# 501_GridPos5.net
KiCad netlist of a schematic drawn in Altium Designer
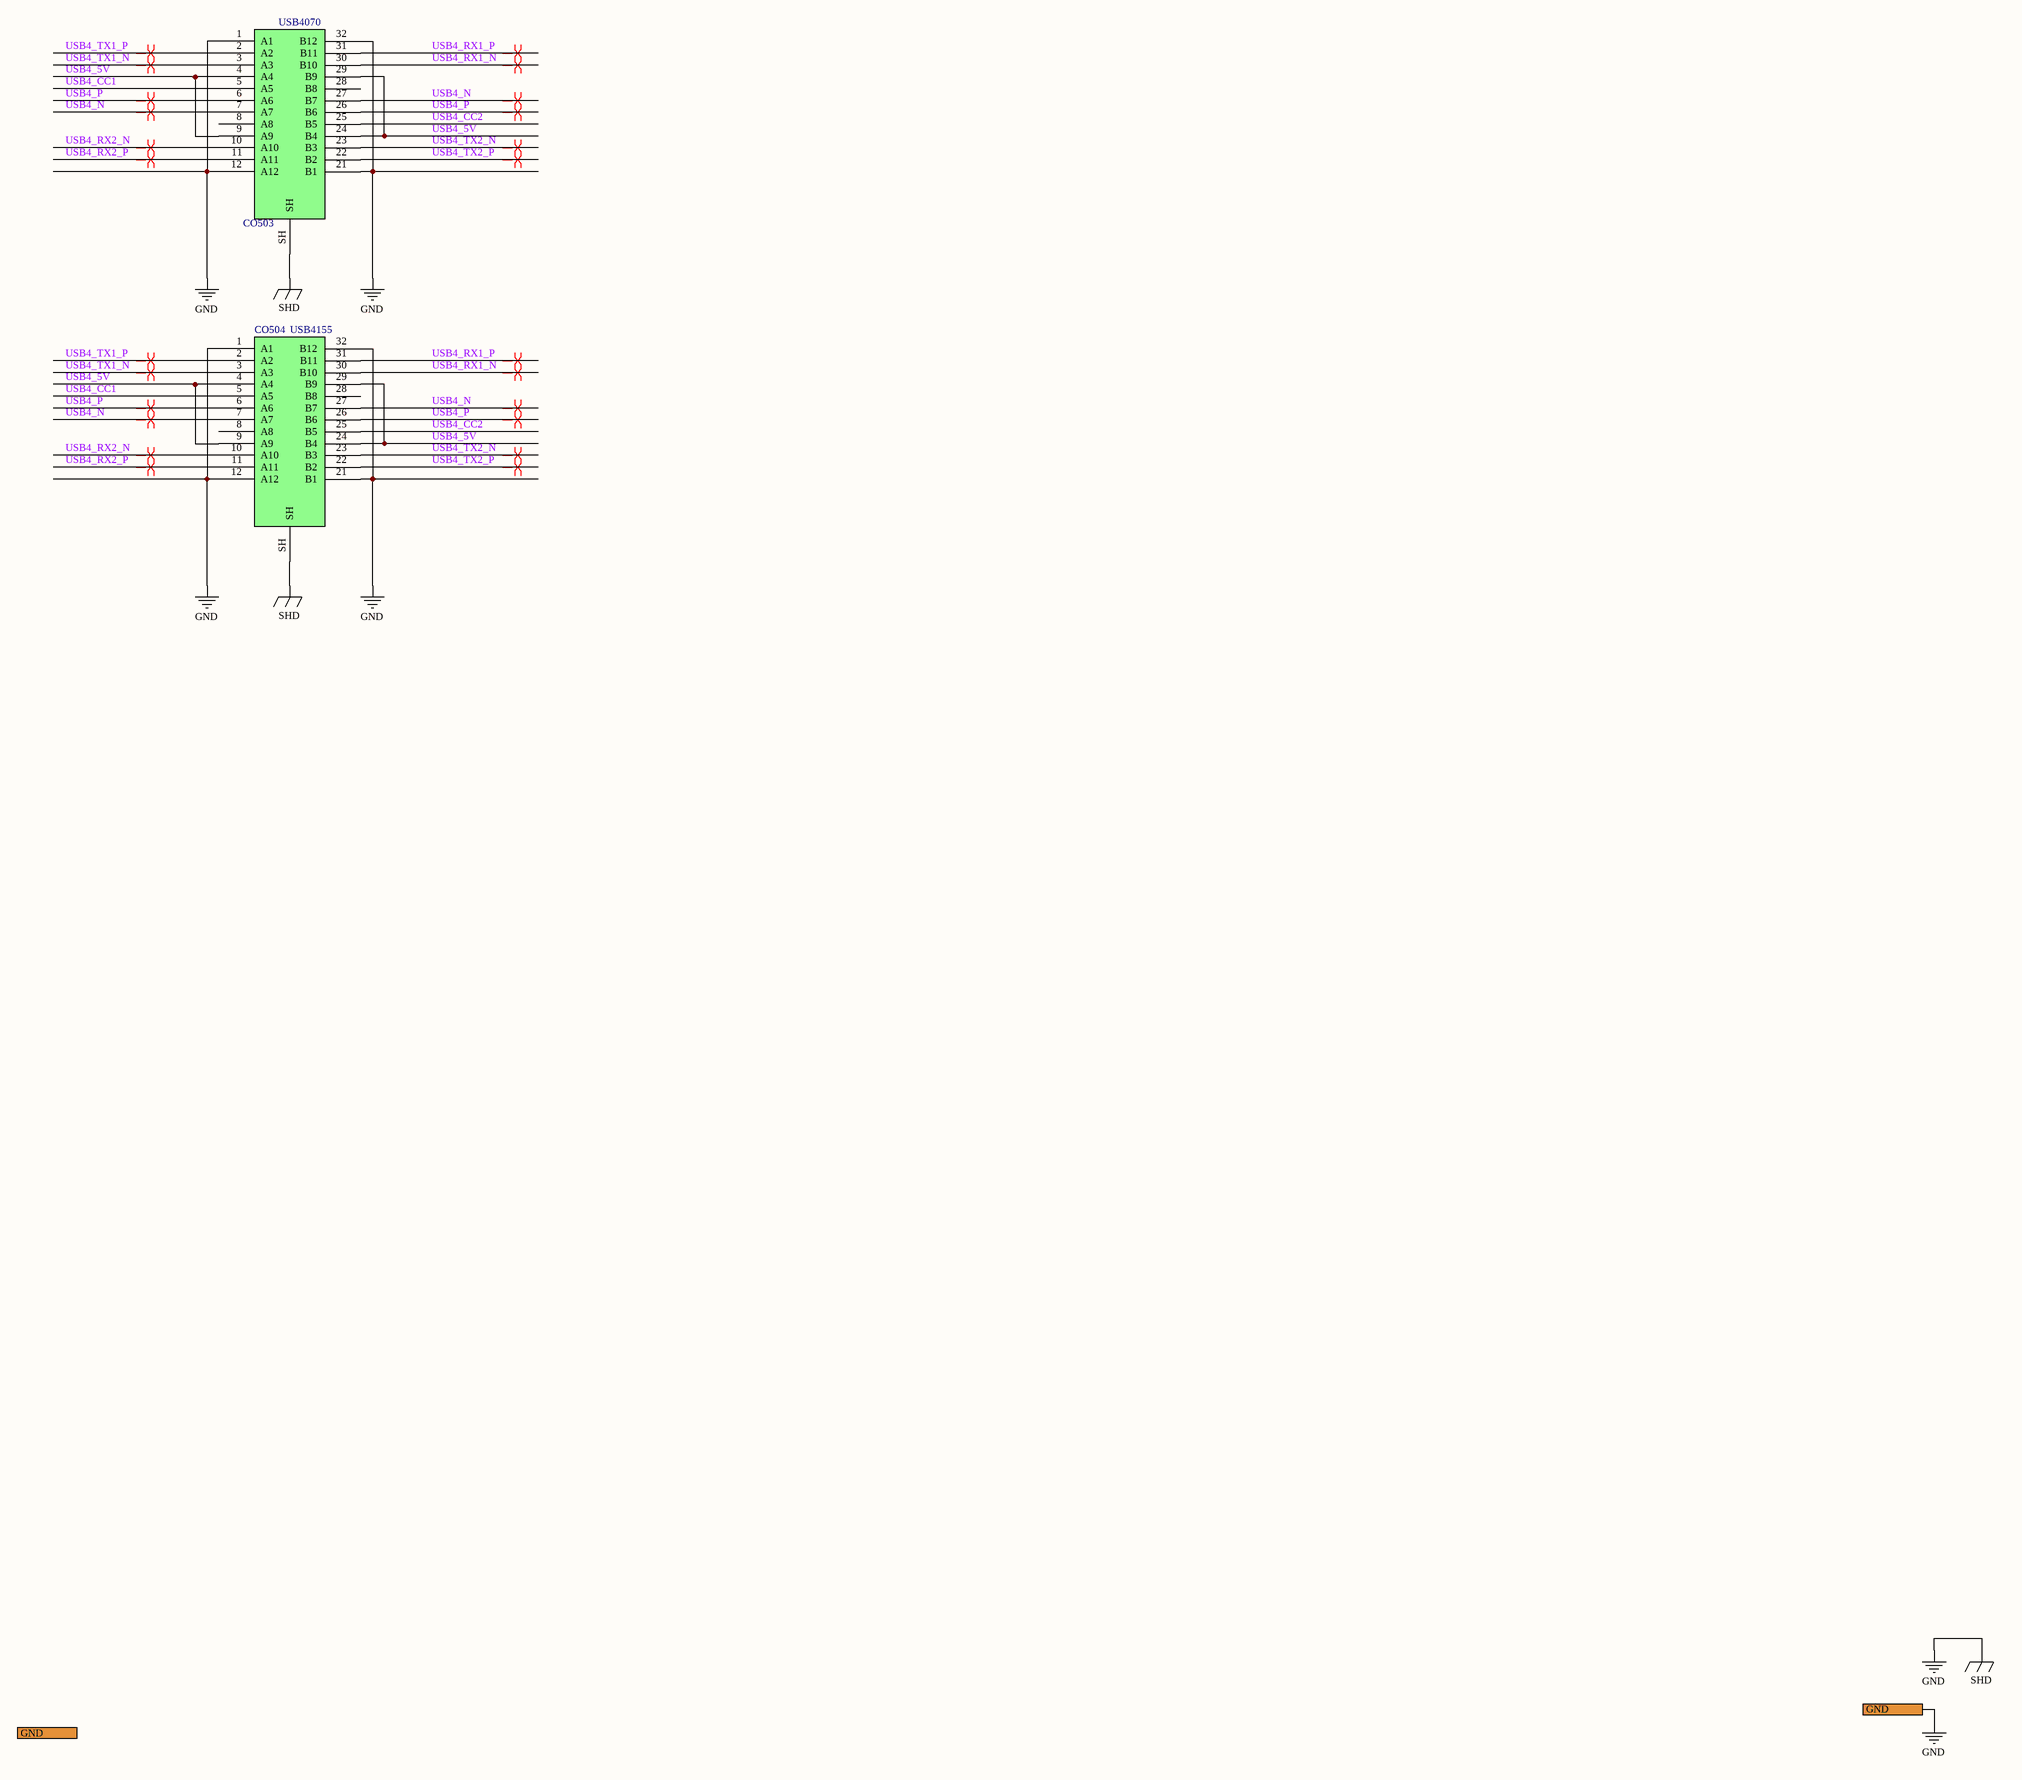
[diagram p0: 501_GridPos5.SchDoc]

(export (version "E")
  (design (tool "Eeschema 10.0.6"))
  (components
    (comp (ref "CO503")
      (value "USB4070")
      (footprint "USB4070-30-C")
      (description "USB C connector Receptacle Vertical")
      (fields
        (field (name "REFVAL") "USB4070")
        (field (name "PART NUMBER") "CO0021")
        (field (name "MANFACTPART") "USB4070-30-C")
      )
      (libsource (lib "GTS_Database") (part "USB-CC"))
    )
    (comp (ref "CO504")
      (value "USB4155")
      (footprint "USB4155-03-C")
      (description "USB C connector Plug Horizontal")
      (fields
        (field (name "REFVAL") "USB4155")
        (field (name "PART NUMBER") "CO0031")
        (field (name "MANFACTPART") "USB4155-03-C")
      )
      (libsource (lib "GTS_Database") (part "USB-CC"))
    )
  )
  (nets
    (net (code "1") (name "/USB4_5V") (class "Default")
      (node (ref "CO503") (pin "24") (pinfunction "B4_24") (pintype "passive"))
      (node (ref "CO503") (pin "29") (pinfunction "B9_29") (pintype "passive"))
      (node (ref "CO503") (pin "4") (pinfunction "A4_4") (pintype "passive"))
      (node (ref "CO503") (pin "9") (pinfunction "A9_9") (pintype "passive"))
      (node (ref "CO504") (pin "24") (pinfunction "B4_24") (pintype "passive"))
      (node (ref "CO504") (pin "29") (pinfunction "B9_29") (pintype "passive"))
      (node (ref "CO504") (pin "4") (pinfunction "A4_4") (pintype "passive"))
      (node (ref "CO504") (pin "9") (pinfunction "A9_9") (pintype "passive"))
    )
    (net (code "2") (name "/USB4_CC1") (class "Default")
      (node (ref "CO503") (pin "5") (pinfunction "A5_5") (pintype "passive"))
      (node (ref "CO504") (pin "5") (pinfunction "A5_5") (pintype "passive"))
    )
    (net (code "3") (name "/USB4_CC2") (class "Default")
      (node (ref "CO503") (pin "25") (pinfunction "B5_25") (pintype "passive"))
      (node (ref "CO504") (pin "25") (pinfunction "B5_25") (pintype "passive"))
    )
    (net (code "4") (name "/USB4_N") (class "Default")
      (node (ref "CO503") (pin "27") (pinfunction "B7_27") (pintype "passive"))
      (node (ref "CO503") (pin "7") (pinfunction "A7_7") (pintype "passive"))
      (node (ref "CO504") (pin "27") (pinfunction "B7_27") (pintype "passive"))
      (node (ref "CO504") (pin "7") (pinfunction "A7_7") (pintype "passive"))
    )
    (net (code "5") (name "/USB4_P") (class "Default")
      (node (ref "CO503") (pin "26") (pinfunction "B6_26") (pintype "passive"))
      (node (ref "CO503") (pin "6") (pinfunction "A6_6") (pintype "passive"))
      (node (ref "CO504") (pin "26") (pinfunction "B6_26") (pintype "passive"))
      (node (ref "CO504") (pin "6") (pinfunction "A6_6") (pintype "passive"))
    )
    (net (code "6") (name "/USB4_RX1_N") (class "Default")
      (node (ref "CO503") (pin "30") (pinfunction "B10_30") (pintype "passive"))
      (node (ref "CO504") (pin "30") (pinfunction "B10_30") (pintype "passive"))
    )
    (net (code "7") (name "/USB4_RX1_P") (class "Default")
      (node (ref "CO503") (pin "31") (pinfunction "B11_31") (pintype "passive"))
      (node (ref "CO504") (pin "31") (pinfunction "B11_31") (pintype "passive"))
    )
    (net (code "8") (name "/USB4_RX2_N") (class "Default")
      (node (ref "CO503") (pin "10") (pinfunction "A10_10") (pintype "passive"))
      (node (ref "CO504") (pin "10") (pinfunction "A10_10") (pintype "passive"))
    )
    (net (code "9") (name "/USB4_RX2_P") (class "Default")
      (node (ref "CO503") (pin "11") (pinfunction "A11_11") (pintype "passive"))
      (node (ref "CO504") (pin "11") (pinfunction "A11_11") (pintype "passive"))
    )
    (net (code "10") (name "/USB4_TX1_N") (class "Default")
      (node (ref "CO503") (pin "3") (pinfunction "A3_3") (pintype "passive"))
      (node (ref "CO504") (pin "3") (pinfunction "A3_3") (pintype "passive"))
    )
    (net (code "11") (name "/USB4_TX1_P") (class "Default")
      (node (ref "CO503") (pin "2") (pinfunction "A2_2") (pintype "passive"))
      (node (ref "CO504") (pin "2") (pinfunction "A2_2") (pintype "passive"))
    )
    (net (code "12") (name "/USB4_TX2_N") (class "Default")
      (node (ref "CO503") (pin "23") (pinfunction "B3_23") (pintype "passive"))
      (node (ref "CO504") (pin "23") (pinfunction "B3_23") (pintype "passive"))
    )
    (net (code "13") (name "/USB4_TX2_P") (class "Default")
      (node (ref "CO503") (pin "22") (pinfunction "B2_22") (pintype "passive"))
      (node (ref "CO504") (pin "22") (pinfunction "B2_22") (pintype "passive"))
    )
    (net (code "14") (name "GND") (class "Default")
      (node (ref "CO503") (pin "1") (pinfunction "A1_1") (pintype "passive"))
      (node (ref "CO503") (pin "12") (pinfunction "A12_12") (pintype "passive"))
      (node (ref "CO503") (pin "21") (pinfunction "B1_21") (pintype "passive"))
      (node (ref "CO503") (pin "32") (pinfunction "B12_32") (pintype "passive"))
      (node (ref "CO503") (pin "SH") (pinfunction "SH_SH") (pintype "power_in"))
      (node (ref "CO504") (pin "1") (pinfunction "A1_1") (pintype "passive"))
      (node (ref "CO504") (pin "12") (pinfunction "A12_12") (pintype "passive"))
      (node (ref "CO504") (pin "21") (pinfunction "B1_21") (pintype "passive"))
      (node (ref "CO504") (pin "32") (pinfunction "B12_32") (pintype "passive"))
      (node (ref "CO504") (pin "SH") (pinfunction "SH_SH") (pintype "power_in"))
    )
    (net (code "15") (name "unconnected-(CO503-A8-Pad8)") (class "Default")
      (node (ref "CO503") (pin "8") (pinfunction "A8_8") (pintype "passive"))
    )
    (net (code "16") (name "unconnected-(CO503-B8-Pad28)") (class "Default")
      (node (ref "CO503") (pin "28") (pinfunction "B8_28") (pintype "passive"))
    )
    (net (code "17") (name "unconnected-(CO504-A8-Pad8)") (class "Default")
      (node (ref "CO504") (pin "8") (pinfunction "A8_8") (pintype "passive"))
    )
    (net (code "18") (name "unconnected-(CO504-B8-Pad28)") (class "Default")
      (node (ref "CO504") (pin "28") (pinfunction "B8_28") (pintype "passive"))
    )
  )
)
